# AD9833_Single_Ended.net
KiCad netlist of a schematic drawn in Altium Designer
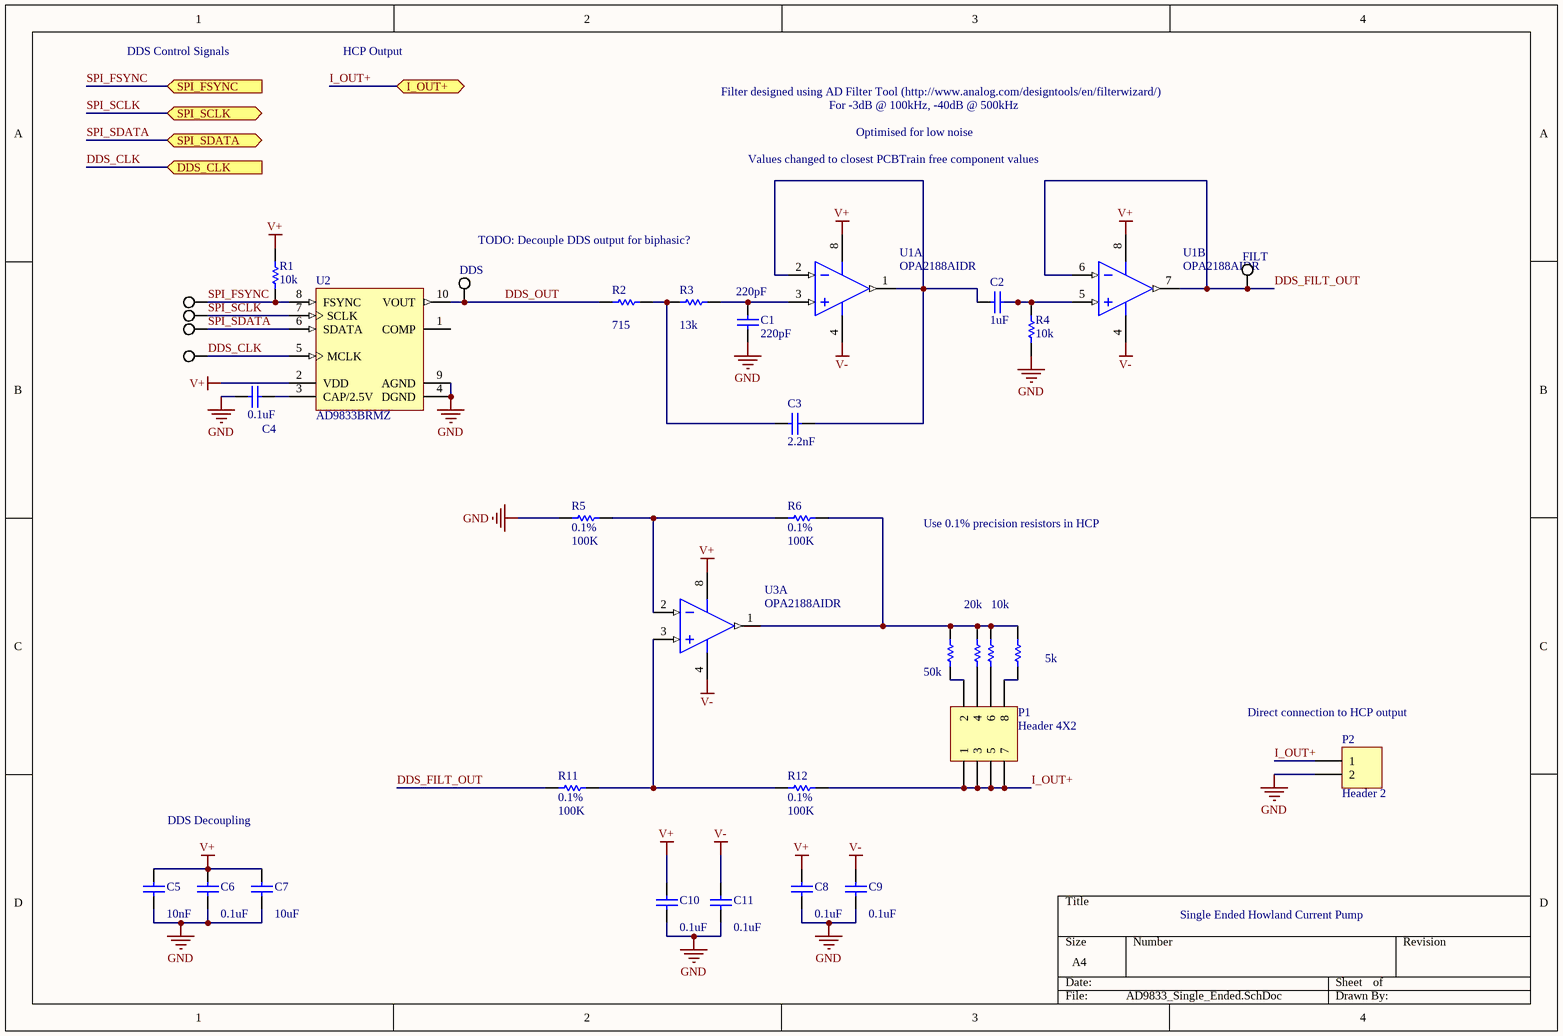
[diagram p0: AD9833_Single_Ended.SchDoc]

(export (version "E")
  (design (tool "Eeschema 10.0.6"))
  (components
    (comp (ref "C1")
      (value "220pF")
      (footprint "1608[0603]")
      (description "Capacitor (Semiconductor SIM Model)")
      (fields (field (name "ALTIUM_VALUE") "220pF") (field (name "PUBLISHER") "Altium Limited"))
      (libsource (lib "Miscellaneous Devices") (part "Cap Semi"))
    )
    (comp (ref "C2")
      (value "1uF")
      (footprint "1608[0603]")
      (description "Capacitor (Semiconductor SIM Model)")
      (fields (field (name "PUBLISHER") "Altium Limited"))
      (libsource (lib "Miscellaneous Devices") (part "Cap Semi"))
    )
    (comp (ref "C3")
      (value "2.2nF")
      (footprint "1608[0603]")
      (description "Capacitor (Semiconductor SIM Model)")
      (fields (field (name "PUBLISHER") "Altium Limited"))
      (libsource (lib "Miscellaneous Devices") (part "Cap Semi"))
    )
    (comp (ref "C4")
      (value "0.1uF")
      (footprint "1608[0603]")
      (description "Capacitor (Semiconductor SIM Model)")
      (fields (field (name "PUBLISHER") "Altium Limited"))
      (libsource (lib "Miscellaneous Devices") (part "Cap Semi"))
    )
    (comp (ref "C5")
      (value "10nF")
      (footprint "1608[0603]")
      (description "Capacitor (Semiconductor SIM Model)")
      (fields (field (name "PUBLISHER") "Altium Limited"))
      (libsource (lib "Miscellaneous Devices") (part "Cap Semi"))
    )
    (comp (ref "C6")
      (value "0.1uF")
      (footprint "1608[0603]")
      (description "Capacitor (Semiconductor SIM Model)")
      (fields (field (name "PUBLISHER") "Altium Limited"))
      (libsource (lib "Miscellaneous Devices") (part "Cap Semi"))
    )
    (comp (ref "C7")
      (value "10uF")
      (footprint "1608[0603]")
      (description "Capacitor (Semiconductor SIM Model)")
      (fields (field (name "PUBLISHER") "Altium Limited"))
      (libsource (lib "Miscellaneous Devices") (part "Cap Semi"))
    )
    (comp (ref "C8")
      (value "0.1uF")
      (footprint "1608[0603]")
      (description "Capacitor (Semiconductor SIM Model)")
      (fields (field (name "PUBLISHER") "Altium Limited"))
      (libsource (lib "Miscellaneous Devices") (part "Cap Semi"))
    )
    (comp (ref "C9")
      (value "0.1uF")
      (footprint "1608[0603]")
      (description "Capacitor (Semiconductor SIM Model)")
      (fields (field (name "PUBLISHER") "Altium Limited"))
      (libsource (lib "Miscellaneous Devices") (part "Cap Semi"))
    )
    (comp (ref "C10")
      (value "0.1uF")
      (footprint "1608[0603]")
      (description "Capacitor (Semiconductor SIM Model)")
      (fields (field (name "PUBLISHER") "Altium Limited"))
      (libsource (lib "Miscellaneous Devices") (part "Cap Semi"))
    )
    (comp (ref "C11")
      (value "0.1uF")
      (footprint "1608[0603]")
      (description "Capacitor (Semiconductor SIM Model)")
      (fields (field (name "PUBLISHER") "Altium Limited"))
      (libsource (lib "Miscellaneous Devices") (part "Cap Semi"))
    )
    (comp (ref "CLK")
      (value "TESTPOINT_WHITE")
      (footprint "TestPointVia")
      (libsource (lib "altium-import") (part "root_1_TESTPOINT_WHITE_"))
    )
    (comp (ref "DDS")
      (value "TESTPOINT_WHITE")
      (footprint "TestPointVia")
      (libsource (lib "altium-import") (part "root_0_TESTPOINT_WHITE_"))
    )
    (comp (ref "FILT")
      (value "TESTPOINT_WHITE")
      (footprint "TestPointVia")
      (libsource (lib "altium-import") (part "root_0_TESTPOINT_WHITE_"))
    )
    (comp (ref "FSYNC")
      (value "TESTPOINT_WHITE")
      (footprint "TestPointVia")
      (libsource (lib "altium-import") (part "root_1_TESTPOINT_WHITE_"))
    )
    (comp (ref "P1")
      (value "Header 4X2")
      (footprint "HDR2X4")
      (description "Header, 4-Pin, Dual row")
      (fields (field (name "PUBLISHER") "Altium Limited"))
      (libsource (lib "Miscellaneous Connectors") (part "Header 4X2"))
    )
    (comp (ref "P2")
      (value "Header 2")
      (footprint "HDR1X2")
      (description "Header, 2-Pin")
      (fields (field (name "PUBLISHER") "Altium Limited"))
      (libsource (lib "Miscellaneous Connectors") (part "Header 2"))
    )
    (comp (ref "R1")
      (value "10k")
      (footprint "6-0805_M")
      (description "Resistor")
      (fields (field (name "PUBLISHER") "Altium Limited"))
      (libsource (lib "Miscellaneous Devices") (part "Res1"))
    )
    (comp (ref "R2")
      (value "715")
      (footprint "6-0805_M")
      (description "Resistor")
      (fields (field (name "PUBLISHER") "Altium Limited"))
      (libsource (lib "Miscellaneous Devices") (part "Res1"))
    )
    (comp (ref "R3")
      (value "13k")
      (footprint "6-0805_M")
      (description "Resistor")
      (fields (field (name "PUBLISHER") "Altium Limited"))
      (libsource (lib "Miscellaneous Devices") (part "Res1"))
    )
    (comp (ref "R4")
      (value "10k")
      (footprint "6-0805_M")
      (description "Resistor")
      (fields (field (name "PUBLISHER") "Altium Limited"))
      (libsource (lib "Miscellaneous Devices") (part "Res1"))
    )
    (comp (ref "R5")
      (value "0.1%")
      (footprint "6-0805_M")
      (description "Resistor")
      (fields (field (name "ALTIUM_VALUE") "100K") (field (name "PUBLISHER") "Altium Limited"))
      (libsource (lib "Miscellaneous Devices") (part "Res1"))
    )
    (comp (ref "R6")
      (value "0.1%")
      (footprint "6-0805_M")
      (description "Resistor")
      (fields (field (name "ALTIUM_VALUE") "100K") (field (name "PUBLISHER") "Altium Limited"))
      (libsource (lib "Miscellaneous Devices") (part "Res1"))
    )
    (comp (ref "R7")
      (value "50k")
      (footprint "6-0805_M")
      (description "Resistor")
      (fields (field (name "PUBLISHER") "Altium Limited"))
      (libsource (lib "Miscellaneous Devices") (part "Res1"))
    )
    (comp (ref "R8")
      (value "20k")
      (footprint "6-0805_M")
      (description "Resistor")
      (fields (field (name "PUBLISHER") "Altium Limited"))
      (libsource (lib "Miscellaneous Devices") (part "Res1"))
    )
    (comp (ref "R9")
      (value "10k")
      (footprint "6-0805_M")
      (description "Resistor")
      (fields (field (name "PUBLISHER") "Altium Limited"))
      (libsource (lib "Miscellaneous Devices") (part "Res1"))
    )
    (comp (ref "R10")
      (value "5k")
      (footprint "6-0805_M")
      (description "Resistor")
      (fields (field (name "PUBLISHER") "Altium Limited"))
      (libsource (lib "Miscellaneous Devices") (part "Res1"))
    )
    (comp (ref "R11")
      (value "0.1%")
      (footprint "6-0805_M")
      (description "Resistor")
      (fields (field (name "ALTIUM_VALUE") "100K") (field (name "PUBLISHER") "Altium Limited"))
      (libsource (lib "Miscellaneous Devices") (part "Res1"))
    )
    (comp (ref "R12")
      (value "0.1%")
      (footprint "6-0805_M")
      (description "Resistor")
      (fields (field (name "ALTIUM_VALUE") "100K") (field (name "PUBLISHER") "Altium Limited"))
      (libsource (lib "Miscellaneous Devices") (part "Res1"))
    )
    (comp (ref "SCLK")
      (value "TESTPOINT_WHITE")
      (footprint "TestPointVia")
      (libsource (lib "altium-import") (part "root_1_TESTPOINT_WHITE_"))
    )
    (comp (ref "SDAT")
      (value "TESTPOINT_WHITE")
      (footprint "TestPointVia")
      (libsource (lib "altium-import") (part "root_1_TESTPOINT_WHITE_"))
    )
    (comp (ref "U1")
      (value "OPA2188AIDR")
      (footprint "D0008A_L")
      (fields (field (name "MANUFACTURER") "Texas Instruments"))
      (libsource (lib "Altium Content Vault") (part "TI-OPA-8_2"))
    )
    (comp (ref "U2")
      (value "AD9833BRMZ")
      (footprint "ADI-RM-10_M")
      (libsource (lib "Altium Content Vault") (part "ADI-AD9833-RM-10"))
    )
    (comp (ref "U3")
      (value "OPA2188AIDR")
      (footprint "D0008A_L")
      (fields (field (name "MANUFACTURER") "Texas Instruments"))
      (libsource (lib "Altium Content Vault") (part "TI-OPA-8_2"))
    )
  )
  (nets
    (net (code "1") (name "/DDS_CLK") (class "Default")
      (node (ref "CLK") (pin "1") (pinfunction "1_1") (pintype "passive"))
      (node (ref "U2") (pin "5") (pinfunction "MCLK_5") (pintype "input"))
    )
    (net (code "2") (name "/DDS_FILT_OUT") (class "Default")
      (node (ref "FILT") (pin "1") (pinfunction "1_1") (pintype "passive"))
      (node (ref "R11") (pin "1") (pinfunction "1_1") (pintype "passive"))
      (node (ref "U1") (pin "6") (pinfunction "IN_B-_6") (pintype "input"))
      (node (ref "U1") (pin "7") (pinfunction "OUT_B_7") (pintype "output"))
    )
    (net (code "3") (name "/DDS_OUT") (class "Default")
      (node (ref "DDS") (pin "1") (pinfunction "1_1") (pintype "passive"))
      (node (ref "R2") (pin "1") (pinfunction "1_1") (pintype "passive"))
      (node (ref "U2") (pin "10") (pinfunction "VOUT_10") (pintype "output"))
    )
    (net (code "4") (name "/I_OUT+") (class "Default")
      (node (ref "P1") (pin "1") (pinfunction "1_1") (pintype "passive"))
      (node (ref "P1") (pin "3") (pinfunction "3_3") (pintype "passive"))
      (node (ref "P1") (pin "5") (pinfunction "5_5") (pintype "passive"))
      (node (ref "P1") (pin "7") (pinfunction "7_7") (pintype "passive"))
      (node (ref "P2") (pin "1") (pinfunction "1_1") (pintype "passive"))
      (node (ref "R12") (pin "2") (pinfunction "2_2") (pintype "passive"))
    )
    (net (code "5") (name "/SPI_FSYNC") (class "Default")
      (node (ref "FSYNC") (pin "1") (pinfunction "1_1") (pintype "passive"))
      (node (ref "R1") (pin "1") (pinfunction "1_1") (pintype "passive"))
      (node (ref "U2") (pin "8") (pinfunction "FSYNC_8") (pintype "input"))
    )
    (net (code "6") (name "/SPI_SCLK") (class "Default")
      (node (ref "SCLK") (pin "1") (pinfunction "1_1") (pintype "passive"))
      (node (ref "U2") (pin "7") (pinfunction "SCLK_7") (pintype "input"))
    )
    (net (code "7") (name "/SPI_SDATA") (class "Default")
      (node (ref "SDAT") (pin "1") (pinfunction "1_1") (pintype "passive"))
      (node (ref "U2") (pin "6") (pinfunction "SDATA_6") (pintype "input"))
    )
    (net (code "8") (name "GND") (class "Default")
      (node (ref "C1") (pin "1") (pinfunction "1_1") (pintype "passive"))
      (node (ref "C10") (pin "1") (pinfunction "1_1") (pintype "passive"))
      (node (ref "C11") (pin "1") (pinfunction "1_1") (pintype "passive"))
      (node (ref "C4") (pin "1") (pinfunction "1_1") (pintype "passive"))
      (node (ref "C5") (pin "1") (pinfunction "1_1") (pintype "passive"))
      (node (ref "C6") (pin "1") (pinfunction "1_1") (pintype "passive"))
      (node (ref "C7") (pin "1") (pinfunction "1_1") (pintype "passive"))
      (node (ref "C8") (pin "1") (pinfunction "1_1") (pintype "passive"))
      (node (ref "C9") (pin "1") (pinfunction "1_1") (pintype "passive"))
      (node (ref "P2") (pin "2") (pinfunction "2_2") (pintype "passive"))
      (node (ref "R4") (pin "1") (pinfunction "1_1") (pintype "passive"))
      (node (ref "R5") (pin "1") (pinfunction "1_1") (pintype "passive"))
      (node (ref "U2") (pin "4") (pinfunction "DGND_4") (pintype "power_in"))
      (node (ref "U2") (pin "9") (pinfunction "AGND_9") (pintype "power_in"))
    )
    (net (code "9") (name "Net-(C3-Pad2)") (class "Default")
      (node (ref "C3") (pin "2") (pinfunction "2_2") (pintype "passive"))
      (node (ref "R2") (pin "2") (pinfunction "2_2") (pintype "passive"))
      (node (ref "R3") (pin "1") (pinfunction "1_1") (pintype "passive"))
    )
    (net (code "10") (name "Net-(P1-Pad2)") (class "Default")
      (node (ref "P1") (pin "2") (pinfunction "2_2") (pintype "passive"))
      (node (ref "R7") (pin "1") (pinfunction "1_1") (pintype "passive"))
    )
    (net (code "11") (name "Net-(P1-Pad4)") (class "Default")
      (node (ref "P1") (pin "4") (pinfunction "4_4") (pintype "passive"))
      (node (ref "R8") (pin "2") (pinfunction "2_2") (pintype "passive"))
    )
    (net (code "12") (name "Net-(P1-Pad6)") (class "Default")
      (node (ref "P1") (pin "6") (pinfunction "6_6") (pintype "passive"))
      (node (ref "R9") (pin "2") (pinfunction "2_2") (pintype "passive"))
    )
    (net (code "13") (name "Net-(P1-Pad8)") (class "Default")
      (node (ref "P1") (pin "8") (pinfunction "8_8") (pintype "passive"))
      (node (ref "R10") (pin "2") (pinfunction "2_2") (pintype "passive"))
    )
    (net (code "14") (name "Net-(U1A-IN_A+)") (class "Default")
      (node (ref "C1") (pin "2") (pinfunction "2_2") (pintype "passive"))
      (node (ref "R3") (pin "2") (pinfunction "2_2") (pintype "passive"))
      (node (ref "U1") (pin "3") (pinfunction "IN_A+_3") (pintype "input"))
    )
    (net (code "15") (name "Net-(U1A-IN_A-)") (class "Default")
      (node (ref "C2") (pin "1") (pinfunction "1_1") (pintype "passive"))
      (node (ref "C3") (pin "1") (pinfunction "1_1") (pintype "passive"))
      (node (ref "U1") (pin "1") (pinfunction "OUT_A_1") (pintype "output"))
      (node (ref "U1") (pin "2") (pinfunction "IN_A-_2") (pintype "input"))
    )
    (net (code "16") (name "Net-(U1B-IN_B+)") (class "Default")
      (node (ref "C2") (pin "2") (pinfunction "2_2") (pintype "passive"))
      (node (ref "R4") (pin "2") (pinfunction "2_2") (pintype "passive"))
      (node (ref "U1") (pin "5") (pinfunction "IN_B+_5") (pintype "input"))
    )
    (net (code "17") (name "Net-(U2-CAP{slash}2.5V)") (class "Default")
      (node (ref "C4") (pin "2") (pinfunction "2_2") (pintype "passive"))
      (node (ref "U2") (pin "3") (pinfunction "CAP/2.5V_3") (pintype "power_in"))
    )
    (net (code "18") (name "Net-(U3A-IN_A+)") (class "Default")
      (node (ref "R11") (pin "2") (pinfunction "2_2") (pintype "passive"))
      (node (ref "R12") (pin "1") (pinfunction "1_1") (pintype "passive"))
      (node (ref "U3") (pin "3") (pinfunction "IN_A+_3") (pintype "input"))
    )
    (net (code "19") (name "Net-(U3A-IN_A-)") (class "Default")
      (node (ref "R5") (pin "2") (pinfunction "2_2") (pintype "passive"))
      (node (ref "R6") (pin "1") (pinfunction "1_1") (pintype "passive"))
      (node (ref "U3") (pin "2") (pinfunction "IN_A-_2") (pintype "input"))
    )
    (net (code "20") (name "Net-(U3A-OUT_A)") (class "Default")
      (node (ref "R10") (pin "1") (pinfunction "1_1") (pintype "passive"))
      (node (ref "R6") (pin "2") (pinfunction "2_2") (pintype "passive"))
      (node (ref "R7") (pin "2") (pinfunction "2_2") (pintype "passive"))
      (node (ref "R8") (pin "1") (pinfunction "1_1") (pintype "passive"))
      (node (ref "R9") (pin "1") (pinfunction "1_1") (pintype "passive"))
      (node (ref "U3") (pin "1") (pinfunction "OUT_A_1") (pintype "output"))
    )
    (net (code "21") (name "V+") (class "Default")
      (node (ref "C10") (pin "2") (pinfunction "2_2") (pintype "passive"))
      (node (ref "C5") (pin "2") (pinfunction "2_2") (pintype "passive"))
      (node (ref "C6") (pin "2") (pinfunction "2_2") (pintype "passive"))
      (node (ref "C7") (pin "2") (pinfunction "2_2") (pintype "passive"))
      (node (ref "C8") (pin "2") (pinfunction "2_2") (pintype "passive"))
      (node (ref "R1") (pin "2") (pinfunction "2_2") (pintype "passive"))
      (node (ref "U1") (pin "8") (pinfunction "V+_8") (pintype "power_in"))
      (node (ref "U2") (pin "2") (pinfunction "VDD_2") (pintype "power_in"))
      (node (ref "U3") (pin "8") (pinfunction "V+_8") (pintype "power_in"))
    )
    (net (code "22") (name "V-") (class "Default")
      (node (ref "C11") (pin "2") (pinfunction "2_2") (pintype "passive"))
      (node (ref "C9") (pin "2") (pinfunction "2_2") (pintype "passive"))
      (node (ref "U1") (pin "4") (pinfunction "V-_4") (pintype "power_in"))
      (node (ref "U3") (pin "4") (pinfunction "V-_4") (pintype "power_in"))
    )
    (net (code "23") (name "unconnected-(U2-COMP-Pad1)") (class "Default")
      (node (ref "U2") (pin "1") (pinfunction "COMP_1") (pintype "passive"))
    )
  )
)
